# MC21R01_Onboard_temp_sensors.net
KiCad netlist of a schematic drawn in Altium Designer
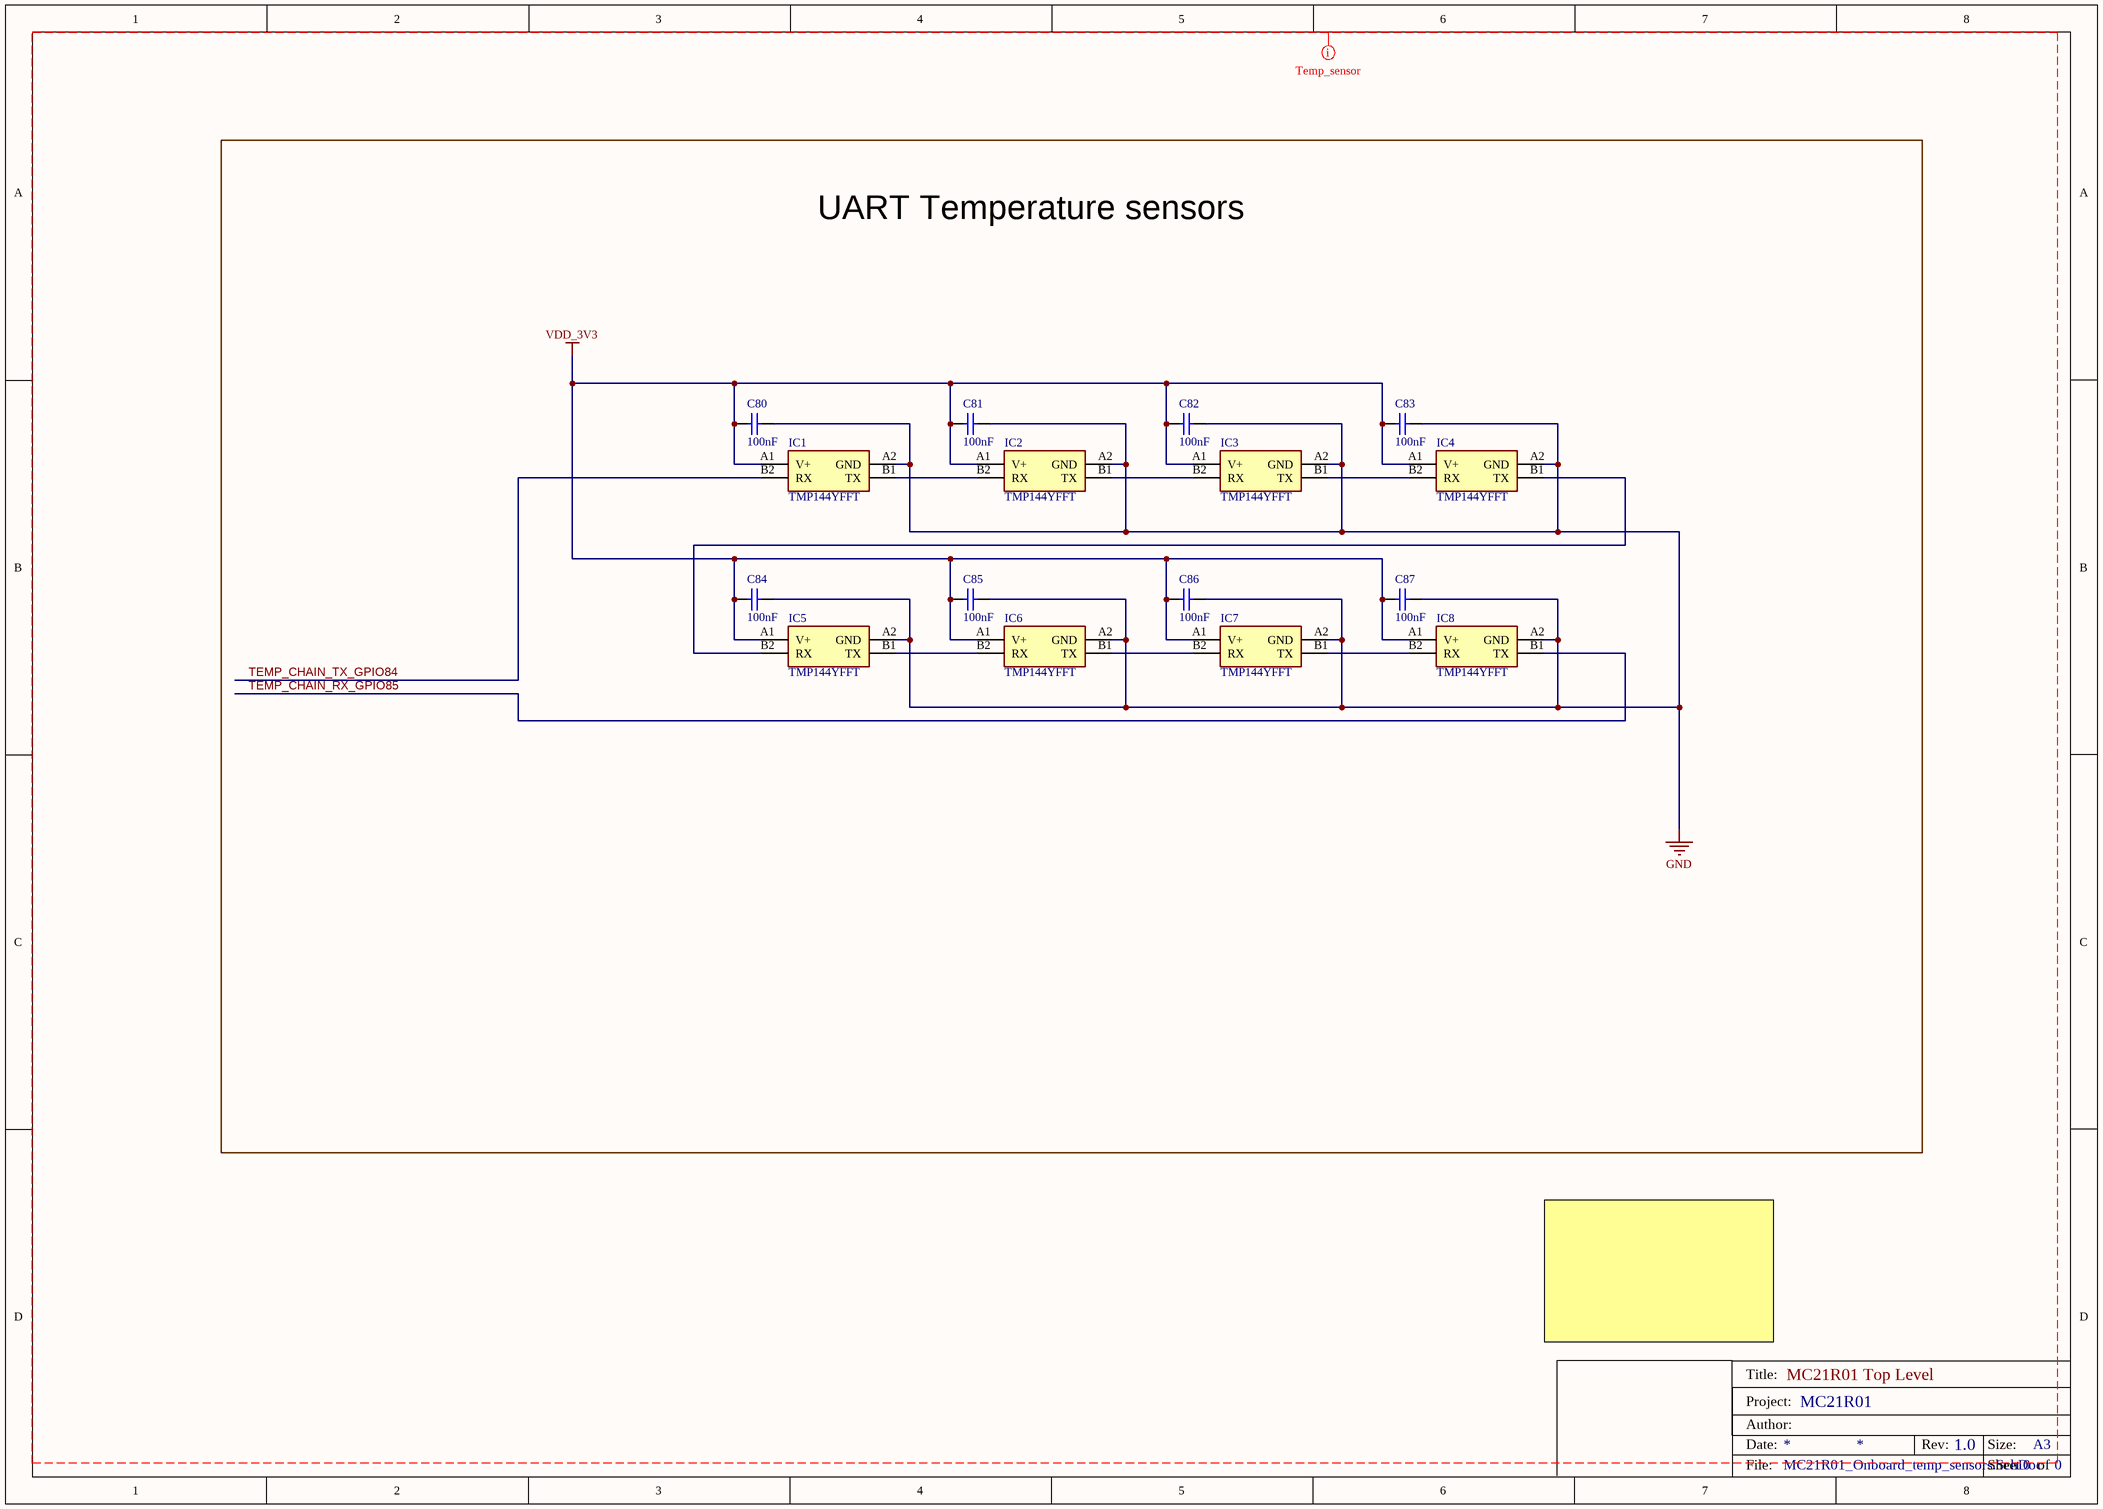
[diagram p0: MC21R01_Onboard_temp_sensors.SchDoc]

(export (version "E")
  (design (tool "Eeschema 10.0.6"))
  (components
    (comp (ref "C80")
      (value "100nF")
      (footprint "CAPC0603X03N")
      (description "100nF/25V 0201 10% Tolerance X6S Multilayer Ceramic Chip Capacitor")
      (fields (field (name "TOLERANCE") "10%") (field (name "Comment") "100nF/25V 0201 10% X6S"))
      (libsource (lib "Wandercraft") (part "STD_CAP_2PIN_NPOL"))
    )
    (comp (ref "C81")
      (value "100nF")
      (footprint "CAPC0603X03N")
      (description "100nF/25V 0201 10% Tolerance X6S Multilayer Ceramic Chip Capacitor")
      (fields (field (name "TOLERANCE") "10%") (field (name "Comment") "100nF/25V 0201 10% X6S"))
      (libsource (lib "Wandercraft") (part "STD_CAP_2PIN_NPOL"))
    )
    (comp (ref "C82")
      (value "100nF")
      (footprint "CAPC0603X03N")
      (description "100nF/25V 0201 10% Tolerance X6S Multilayer Ceramic Chip Capacitor")
      (fields (field (name "TOLERANCE") "10%") (field (name "Comment") "100nF/25V 0201 10% X6S"))
      (libsource (lib "Wandercraft") (part "STD_CAP_2PIN_NPOL"))
    )
    (comp (ref "C83")
      (value "100nF")
      (footprint "CAPC0603X03N")
      (description "100nF/25V 0201 10% Tolerance X6S Multilayer Ceramic Chip Capacitor")
      (fields (field (name "TOLERANCE") "10%") (field (name "Comment") "100nF/25V 0201 10% X6S"))
      (libsource (lib "Wandercraft") (part "STD_CAP_2PIN_NPOL"))
    )
    (comp (ref "C84")
      (value "100nF")
      (footprint "CAPC0603X03N")
      (description "100nF/25V 0201 10% Tolerance X6S Multilayer Ceramic Chip Capacitor")
      (fields (field (name "TOLERANCE") "10%") (field (name "Comment") "100nF/25V 0201 10% X6S"))
      (libsource (lib "Wandercraft") (part "STD_CAP_2PIN_NPOL"))
    )
    (comp (ref "C85")
      (value "100nF")
      (footprint "CAPC0603X03N")
      (description "100nF/25V 0201 10% Tolerance X6S Multilayer Ceramic Chip Capacitor")
      (fields (field (name "TOLERANCE") "10%") (field (name "Comment") "100nF/25V 0201 10% X6S"))
      (libsource (lib "Wandercraft") (part "STD_CAP_2PIN_NPOL"))
    )
    (comp (ref "C86")
      (value "100nF")
      (footprint "CAPC0603X03N")
      (description "100nF/25V 0201 10% Tolerance X6S Multilayer Ceramic Chip Capacitor")
      (fields (field (name "TOLERANCE") "10%") (field (name "Comment") "100nF/25V 0201 10% X6S"))
      (libsource (lib "Wandercraft") (part "STD_CAP_2PIN_NPOL"))
    )
    (comp (ref "C87")
      (value "100nF")
      (footprint "CAPC0603X03N")
      (description "100nF/25V 0201 10% Tolerance X6S Multilayer Ceramic Chip Capacitor")
      (fields (field (name "TOLERANCE") "10%") (field (name "Comment") "100nF/25V 0201 10% X6S"))
      (libsource (lib "Wandercraft") (part "STD_CAP_2PIN_NPOL"))
    )
    (comp (ref "IC1")
      (value "TMP144YFFT")
      (footprint "PAL_devices:TMP144YFFT")
      (description "Integrated Circuit")
      (fields (field (name "MOUSER PART NUMBER") "595-TMP144YFFT"))
      (libsource (lib "PAL_devices") (part "TMP144YFFT"))
    )
    (comp (ref "IC2")
      (value "TMP144YFFT")
      (footprint "PAL_devices:TMP144YFFT")
      (description "Integrated Circuit")
      (fields (field (name "MOUSER PART NUMBER") "595-TMP144YFFT"))
      (libsource (lib "PAL_devices") (part "TMP144YFFT"))
    )
    (comp (ref "IC3")
      (value "TMP144YFFT")
      (footprint "PAL_devices:TMP144YFFT")
      (description "Integrated Circuit")
      (fields (field (name "MOUSER PART NUMBER") "595-TMP144YFFT"))
      (libsource (lib "PAL_devices") (part "TMP144YFFT"))
    )
    (comp (ref "IC4")
      (value "TMP144YFFT")
      (footprint "PAL_devices:TMP144YFFT")
      (description "Integrated Circuit")
      (fields (field (name "MOUSER PART NUMBER") "595-TMP144YFFT"))
      (libsource (lib "PAL_devices") (part "TMP144YFFT"))
    )
    (comp (ref "IC5")
      (value "TMP144YFFT")
      (footprint "PAL_devices:TMP144YFFT")
      (description "Integrated Circuit")
      (fields (field (name "MOUSER PART NUMBER") "595-TMP144YFFT"))
      (libsource (lib "PAL_devices") (part "TMP144YFFT"))
    )
    (comp (ref "IC6")
      (value "TMP144YFFT")
      (footprint "PAL_devices:TMP144YFFT")
      (description "Integrated Circuit")
      (fields (field (name "MOUSER PART NUMBER") "595-TMP144YFFT"))
      (libsource (lib "PAL_devices") (part "TMP144YFFT"))
    )
    (comp (ref "IC7")
      (value "TMP144YFFT")
      (footprint "PAL_devices:TMP144YFFT")
      (description "Integrated Circuit")
      (fields (field (name "MOUSER PART NUMBER") "595-TMP144YFFT"))
      (libsource (lib "PAL_devices") (part "TMP144YFFT"))
    )
    (comp (ref "IC8")
      (value "TMP144YFFT")
      (footprint "PAL_devices:TMP144YFFT")
      (description "Integrated Circuit")
      (fields (field (name "MOUSER PART NUMBER") "595-TMP144YFFT"))
      (libsource (lib "PAL_devices") (part "TMP144YFFT"))
    )
  )
  (nets
    (net (code "1") (name "/TEMP_CHAIN_RX_GPIO85") (class "Default")
      (node (ref "IC8") (pin "B1") (pinfunction "TX_B1") (pintype "passive"))
    )
    (net (code "2") (name "/TEMP_CHAIN_TX_GPIO84") (class "Default")
      (node (ref "IC1") (pin "B2") (pinfunction "RX_B2") (pintype "passive"))
    )
    (net (code "3") (name "GND") (class "Default")
      (node (ref "C80") (pin "1") (pinfunction "1_1") (pintype "passive"))
      (node (ref "C81") (pin "1") (pinfunction "1_1") (pintype "passive"))
      (node (ref "C82") (pin "1") (pinfunction "1_1") (pintype "passive"))
      (node (ref "C83") (pin "1") (pinfunction "1_1") (pintype "passive"))
      (node (ref "C84") (pin "1") (pinfunction "1_1") (pintype "passive"))
      (node (ref "C85") (pin "1") (pinfunction "1_1") (pintype "passive"))
      (node (ref "C86") (pin "1") (pinfunction "1_1") (pintype "passive"))
      (node (ref "C87") (pin "1") (pinfunction "1_1") (pintype "passive"))
      (node (ref "IC1") (pin "A2") (pinfunction "GND_A2") (pintype "passive"))
      (node (ref "IC2") (pin "A2") (pinfunction "GND_A2") (pintype "passive"))
      (node (ref "IC3") (pin "A2") (pinfunction "GND_A2") (pintype "passive"))
      (node (ref "IC4") (pin "A2") (pinfunction "GND_A2") (pintype "passive"))
      (node (ref "IC5") (pin "A2") (pinfunction "GND_A2") (pintype "passive"))
      (node (ref "IC6") (pin "A2") (pinfunction "GND_A2") (pintype "passive"))
      (node (ref "IC7") (pin "A2") (pinfunction "GND_A2") (pintype "passive"))
      (node (ref "IC8") (pin "A2") (pinfunction "GND_A2") (pintype "passive"))
    )
    (net (code "4") (name "Net-(IC1-TX)") (class "Default")
      (node (ref "IC1") (pin "B1") (pinfunction "TX_B1") (pintype "passive"))
      (node (ref "IC2") (pin "B2") (pinfunction "RX_B2") (pintype "passive"))
    )
    (net (code "5") (name "Net-(IC2-TX)") (class "Default")
      (node (ref "IC2") (pin "B1") (pinfunction "TX_B1") (pintype "passive"))
      (node (ref "IC3") (pin "B2") (pinfunction "RX_B2") (pintype "passive"))
    )
    (net (code "6") (name "Net-(IC3-TX)") (class "Default")
      (node (ref "IC3") (pin "B1") (pinfunction "TX_B1") (pintype "passive"))
      (node (ref "IC4") (pin "B2") (pinfunction "RX_B2") (pintype "passive"))
    )
    (net (code "7") (name "Net-(IC4-TX)") (class "Default")
      (node (ref "IC4") (pin "B1") (pinfunction "TX_B1") (pintype "passive"))
      (node (ref "IC5") (pin "B2") (pinfunction "RX_B2") (pintype "passive"))
    )
    (net (code "8") (name "Net-(IC5-TX)") (class "Default")
      (node (ref "IC5") (pin "B1") (pinfunction "TX_B1") (pintype "passive"))
      (node (ref "IC6") (pin "B2") (pinfunction "RX_B2") (pintype "passive"))
    )
    (net (code "9") (name "Net-(IC6-TX)") (class "Default")
      (node (ref "IC6") (pin "B1") (pinfunction "TX_B1") (pintype "passive"))
      (node (ref "IC7") (pin "B2") (pinfunction "RX_B2") (pintype "passive"))
    )
    (net (code "10") (name "Net-(IC7-TX)") (class "Default")
      (node (ref "IC7") (pin "B1") (pinfunction "TX_B1") (pintype "passive"))
      (node (ref "IC8") (pin "B2") (pinfunction "RX_B2") (pintype "passive"))
    )
    (net (code "11") (name "VDD_3V3") (class "Default")
      (node (ref "C80") (pin "2") (pinfunction "2_2") (pintype "passive"))
      (node (ref "C81") (pin "2") (pinfunction "2_2") (pintype "passive"))
      (node (ref "C82") (pin "2") (pinfunction "2_2") (pintype "passive"))
      (node (ref "C83") (pin "2") (pinfunction "2_2") (pintype "passive"))
      (node (ref "C84") (pin "2") (pinfunction "2_2") (pintype "passive"))
      (node (ref "C85") (pin "2") (pinfunction "2_2") (pintype "passive"))
      (node (ref "C86") (pin "2") (pinfunction "2_2") (pintype "passive"))
      (node (ref "C87") (pin "2") (pinfunction "2_2") (pintype "passive"))
      (node (ref "IC1") (pin "A1") (pinfunction "V+_A1") (pintype "passive"))
      (node (ref "IC2") (pin "A1") (pinfunction "V+_A1") (pintype "passive"))
      (node (ref "IC3") (pin "A1") (pinfunction "V+_A1") (pintype "passive"))
      (node (ref "IC4") (pin "A1") (pinfunction "V+_A1") (pintype "passive"))
      (node (ref "IC5") (pin "A1") (pinfunction "V+_A1") (pintype "passive"))
      (node (ref "IC6") (pin "A1") (pinfunction "V+_A1") (pintype "passive"))
      (node (ref "IC7") (pin "A1") (pinfunction "V+_A1") (pintype "passive"))
      (node (ref "IC8") (pin "A1") (pinfunction "V+_A1") (pintype "passive"))
    )
  )
)
